# board.net
KiCad netlist of a schematic drawn in EAGLE
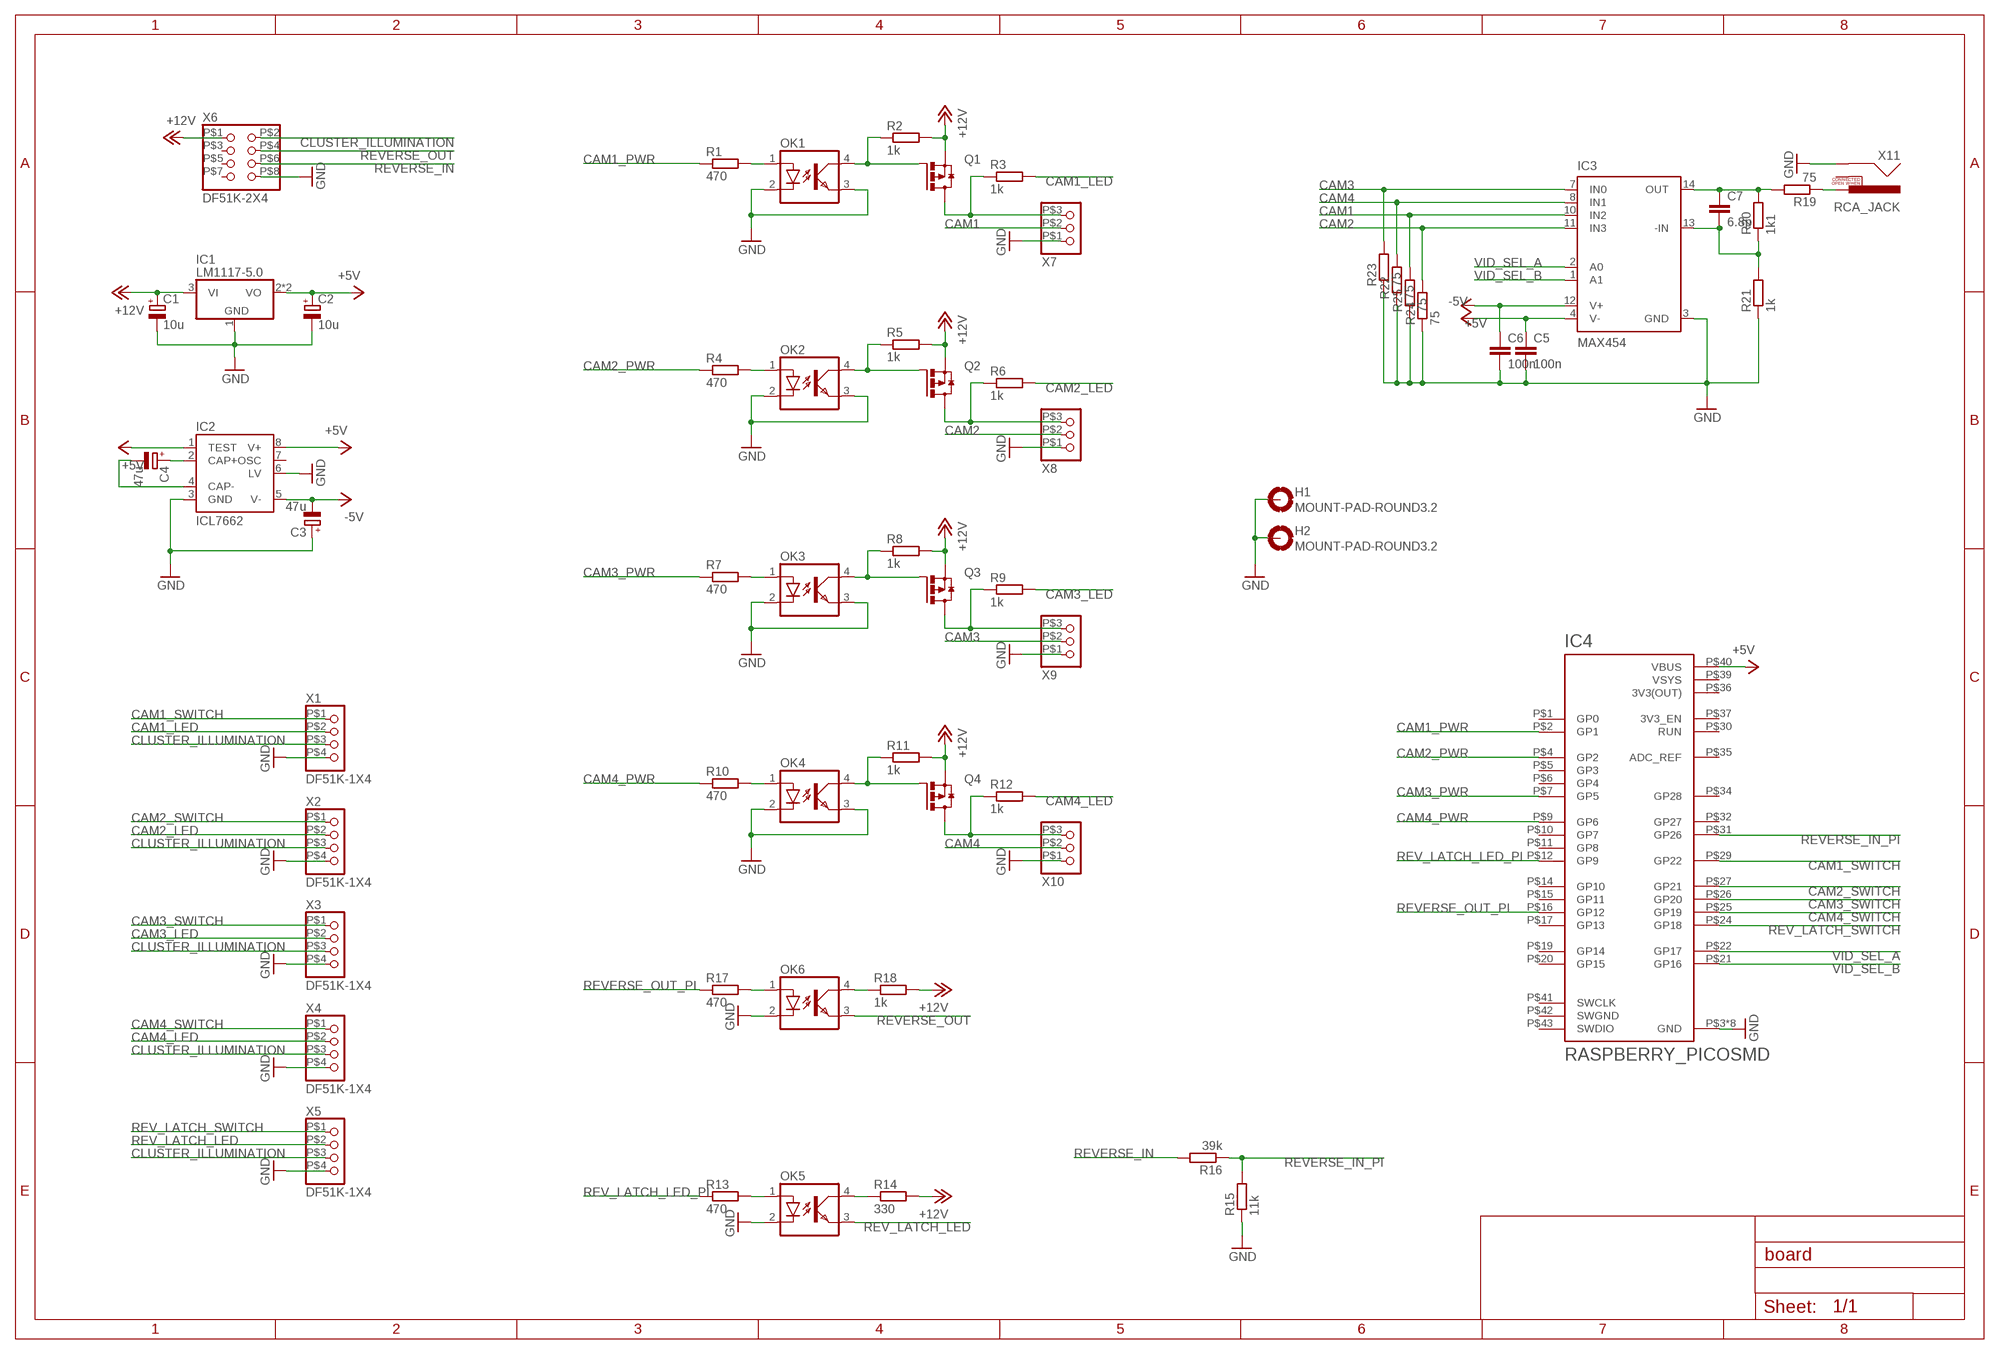
[diagram p0: schematic, sheet 1]

(export (version "E")
  (design (tool "Eeschema 10.0.6"))
  (components
    (comp (ref "C1")
      (value "10u")
      (footprint "eagle-import:C_4MM")
      (libsource (lib "eagle-import") (part "CAPACITOR_POL4MM^2"))
    )
    (comp (ref "C2")
      (value "10u")
      (footprint "eagle-import:C_4MM")
      (libsource (lib "eagle-import") (part "CAPACITOR_POL4MM^2"))
    )
    (comp (ref "C3")
      (value "47u")
      (footprint "eagle-import:CT7343")
      (libsource (lib "eagle-import") (part "CAPACITOR_POL2917"))
    )
    (comp (ref "C4")
      (value "47u")
      (footprint "eagle-import:CT7343")
      (libsource (lib "eagle-import") (part "CAPACITOR_POL2917"))
    )
    (comp (ref "C5")
      (value "100n")
      (footprint "eagle-import:C0805")
      (libsource (lib "eagle-import") (part "CAPACITOR0805"))
    )
    (comp (ref "C6")
      (value "100n")
      (footprint "eagle-import:C0805")
      (libsource (lib "eagle-import") (part "CAPACITOR0805"))
    )
    (comp (ref "C7")
      (value "6.8p")
      (footprint "eagle-import:C0805")
      (libsource (lib "eagle-import") (part "CAPACITOR0805"))
    )
    (comp (ref "H1")
      (value "MOUNT-PAD-ROUND3.2")
      (footprint "eagle-import:3,2-PAD")
      (libsource (lib "eagle-import") (part "MOUNT-PAD-ROUND3.2"))
    )
    (comp (ref "H2")
      (value "MOUNT-PAD-ROUND3.2")
      (footprint "eagle-import:3,2-PAD")
      (libsource (lib "eagle-import") (part "MOUNT-PAD-ROUND3.2"))
    )
    (comp (ref "IC1")
      (value "LM1117-5.0")
      (footprint "eagle-import:SOT223")
      (libsource (lib "eagle-import") (part "LM1117-3.3"))
    )
    (comp (ref "IC2")
      (value "ICL7662")
      (footprint "eagle-import:SO08")
      (libsource (lib "eagle-import") (part "ICL7662"))
    )
    (comp (ref "IC3")
      (value "MAX454")
      (footprint "eagle-import:DIL14")
      (libsource (lib "eagle-import") (part "MAX454"))
    )
    (comp (ref "IC4")
      (value "RASPBERRY_PICOSMD")
      (footprint "eagle-import:PICO-PKG-SMD")
      (libsource (lib "eagle-import") (part "RASPBERRY_PICOSMD"))
    )
    (comp (ref "OK1")
      (value "OPTOCOUPLERSO4")
      (footprint "eagle-import:SO04")
      (libsource (lib "eagle-import") (part "OPTOCOUPLERSO4"))
    )
    (comp (ref "OK2")
      (value "OPTOCOUPLERSO4")
      (footprint "eagle-import:SO04")
      (libsource (lib "eagle-import") (part "OPTOCOUPLERSO4"))
    )
    (comp (ref "OK3")
      (value "OPTOCOUPLERSO4")
      (footprint "eagle-import:SO04")
      (libsource (lib "eagle-import") (part "OPTOCOUPLERSO4"))
    )
    (comp (ref "OK4")
      (value "OPTOCOUPLERSO4")
      (footprint "eagle-import:SO04")
      (libsource (lib "eagle-import") (part "OPTOCOUPLERSO4"))
    )
    (comp (ref "OK5")
      (value "OPTOCOUPLERSO4")
      (footprint "eagle-import:SO04")
      (libsource (lib "eagle-import") (part "OPTOCOUPLERSO4"))
    )
    (comp (ref "OK6")
      (value "OPTOCOUPLERSO4")
      (footprint "eagle-import:SO04")
      (libsource (lib "eagle-import") (part "OPTOCOUPLERSO4"))
    )
    (comp (ref "Q1")
      (value "MOSFET_P_CHANNELSOT23")
      (footprint "eagle-import:SOT23")
      (libsource (lib "eagle-import") (part "MOSFET_P_CHANNELSOT23"))
    )
    (comp (ref "Q2")
      (value "MOSFET_P_CHANNELSOT23")
      (footprint "eagle-import:SOT23")
      (libsource (lib "eagle-import") (part "MOSFET_P_CHANNELSOT23"))
    )
    (comp (ref "Q3")
      (value "MOSFET_P_CHANNELSOT23")
      (footprint "eagle-import:SOT23")
      (libsource (lib "eagle-import") (part "MOSFET_P_CHANNELSOT23"))
    )
    (comp (ref "Q4")
      (value "MOSFET_P_CHANNELSOT23")
      (footprint "eagle-import:SOT23")
      (libsource (lib "eagle-import") (part "MOSFET_P_CHANNELSOT23"))
    )
    (comp (ref "R1")
      (value "470")
      (footprint "eagle-import:R0805")
      (libsource (lib "eagle-import") (part "RESISTOR0805"))
    )
    (comp (ref "R2")
      (value "1k")
      (footprint "eagle-import:R0805")
      (libsource (lib "eagle-import") (part "RESISTOR0805"))
    )
    (comp (ref "R3")
      (value "1k")
      (footprint "eagle-import:R0805")
      (libsource (lib "eagle-import") (part "RESISTOR0805"))
    )
    (comp (ref "R4")
      (value "470")
      (footprint "eagle-import:R0805")
      (libsource (lib "eagle-import") (part "RESISTOR0805"))
    )
    (comp (ref "R5")
      (value "1k")
      (footprint "eagle-import:R0805")
      (libsource (lib "eagle-import") (part "RESISTOR0805"))
    )
    (comp (ref "R6")
      (value "1k")
      (footprint "eagle-import:R0805")
      (libsource (lib "eagle-import") (part "RESISTOR0805"))
    )
    (comp (ref "R7")
      (value "470")
      (footprint "eagle-import:R0805")
      (libsource (lib "eagle-import") (part "RESISTOR0805"))
    )
    (comp (ref "R8")
      (value "1k")
      (footprint "eagle-import:R0805")
      (libsource (lib "eagle-import") (part "RESISTOR0805"))
    )
    (comp (ref "R9")
      (value "1k")
      (footprint "eagle-import:R0805")
      (libsource (lib "eagle-import") (part "RESISTOR0805"))
    )
    (comp (ref "R10")
      (value "470")
      (footprint "eagle-import:R0805")
      (libsource (lib "eagle-import") (part "RESISTOR0805"))
    )
    (comp (ref "R11")
      (value "1k")
      (footprint "eagle-import:R0805")
      (libsource (lib "eagle-import") (part "RESISTOR0805"))
    )
    (comp (ref "R12")
      (value "1k")
      (footprint "eagle-import:R0805")
      (libsource (lib "eagle-import") (part "RESISTOR0805"))
    )
    (comp (ref "R13")
      (value "470")
      (footprint "eagle-import:R0805")
      (libsource (lib "eagle-import") (part "RESISTOR0805"))
    )
    (comp (ref "R14")
      (value "330")
      (footprint "eagle-import:R0805")
      (libsource (lib "eagle-import") (part "RESISTOR0805"))
    )
    (comp (ref "R15")
      (value "11k")
      (footprint "eagle-import:R0805")
      (libsource (lib "eagle-import") (part "RESISTOR0805"))
    )
    (comp (ref "R16")
      (value "39k")
      (footprint "eagle-import:R0805")
      (libsource (lib "eagle-import") (part "RESISTOR0805"))
    )
    (comp (ref "R17")
      (value "470")
      (footprint "eagle-import:R0805")
      (libsource (lib "eagle-import") (part "RESISTOR0805"))
    )
    (comp (ref "R18")
      (value "1k")
      (footprint "eagle-import:R0805")
      (libsource (lib "eagle-import") (part "RESISTOR0805"))
    )
    (comp (ref "R19")
      (value "75")
      (footprint "eagle-import:R0805")
      (libsource (lib "eagle-import") (part "RESISTOR0805"))
    )
    (comp (ref "R20")
      (value "1k1")
      (footprint "eagle-import:R0805")
      (libsource (lib "eagle-import") (part "RESISTOR0805"))
    )
    (comp (ref "R21")
      (value "1k")
      (footprint "eagle-import:R0805")
      (libsource (lib "eagle-import") (part "RESISTOR0805"))
    )
    (comp (ref "R22")
      (value "75")
      (footprint "eagle-import:R0805")
      (libsource (lib "eagle-import") (part "RESISTOR0805"))
    )
    (comp (ref "R23")
      (value "75")
      (footprint "eagle-import:R0805")
      (libsource (lib "eagle-import") (part "RESISTOR0805"))
    )
    (comp (ref "R24")
      (value "75")
      (footprint "eagle-import:R0805")
      (libsource (lib "eagle-import") (part "RESISTOR0805"))
    )
    (comp (ref "R25")
      (value "75")
      (footprint "eagle-import:R0805")
      (libsource (lib "eagle-import") (part "RESISTOR0805"))
    )
    (comp (ref "X1")
      (value "DF51K-1X4")
      (footprint "eagle-import:DF51K-1X4")
      (libsource (lib "eagle-import") (part "DF51K-1X4"))
    )
    (comp (ref "X2")
      (value "DF51K-1X4")
      (footprint "eagle-import:DF51K-1X4")
      (libsource (lib "eagle-import") (part "DF51K-1X4"))
    )
    (comp (ref "X3")
      (value "DF51K-1X4")
      (footprint "eagle-import:DF51K-1X4")
      (libsource (lib "eagle-import") (part "DF51K-1X4"))
    )
    (comp (ref "X4")
      (value "DF51K-1X4")
      (footprint "eagle-import:DF51K-1X4")
      (libsource (lib "eagle-import") (part "DF51K-1X4"))
    )
    (comp (ref "X5")
      (value "DF51K-1X4")
      (footprint "eagle-import:DF51K-1X4")
      (libsource (lib "eagle-import") (part "DF51K-1X4"))
    )
    (comp (ref "X6")
      (value "DF51K-2X4")
      (footprint "eagle-import:DF51K-2X4")
      (libsource (lib "eagle-import") (part "DF51K-2X4"))
    )
    (comp (ref "X7")
      (value "JST_XH_1X3")
      (footprint "eagle-import:JST_XH_1X3")
      (libsource (lib "eagle-import") (part "JST_XH_1X3"))
    )
    (comp (ref "X8")
      (value "JST_XH_1X3")
      (footprint "eagle-import:JST_XH_1X3")
      (libsource (lib "eagle-import") (part "JST_XH_1X3"))
    )
    (comp (ref "X9")
      (value "JST_XH_1X3")
      (footprint "eagle-import:JST_XH_1X3")
      (libsource (lib "eagle-import") (part "JST_XH_1X3"))
    )
    (comp (ref "X10")
      (value "JST_XH_1X3")
      (footprint "eagle-import:JST_XH_1X3")
      (libsource (lib "eagle-import") (part "JST_XH_1X3"))
    )
    (comp (ref "X11")
      (value "RCA_JACK")
      (footprint "eagle-import:RCA_JACK")
      (libsource (lib "eagle-import") (part "RCA_JACK"))
    )
  )
  (nets
    (net (code "1") (name "+5V") (class "Default")
      (node (ref "C2") (pin "+") (pinfunction "+_+") (pintype "passive"))
      (node (ref "C6") (pin "1") (pinfunction "1_1") (pintype "passive"))
      (node (ref "IC1") (pin "2") (pinfunction "VO_2") (pintype "passive"))
      (node (ref "IC1") (pin "4") (pinfunction "VO_4") (pintype "passive"))
      (node (ref "IC2") (pin "1") (pinfunction "TEST_1") (pintype "bidirectional"))
      (node (ref "IC2") (pin "8") (pinfunction "V+_8") (pintype "bidirectional"))
      (node (ref "IC3") (pin "12") (pinfunction "V+_12") (pintype "bidirectional"))
      (node (ref "IC4") (pin "P$40") (pinfunction "VBUS_P$40") (pintype "power_in"))
    )
    (net (code "2") (name "+12V") (class "Default")
      (node (ref "C1") (pin "+") (pinfunction "+_+") (pintype "passive"))
      (node (ref "IC1") (pin "3") (pinfunction "VI_3") (pintype "input"))
      (node (ref "Q1") (pin "2") (pinfunction "S_2") (pintype "passive"))
      (node (ref "Q2") (pin "2") (pinfunction "S_2") (pintype "passive"))
      (node (ref "Q3") (pin "2") (pinfunction "S_2") (pintype "passive"))
      (node (ref "Q4") (pin "2") (pinfunction "S_2") (pintype "passive"))
      (node (ref "R11") (pin "2") (pinfunction "2_2") (pintype "passive"))
      (node (ref "R14") (pin "2") (pinfunction "2_2") (pintype "passive"))
      (node (ref "R18") (pin "2") (pinfunction "2_2") (pintype "passive"))
      (node (ref "R2") (pin "2") (pinfunction "2_2") (pintype "passive"))
      (node (ref "R5") (pin "2") (pinfunction "2_2") (pintype "passive"))
      (node (ref "R8") (pin "2") (pinfunction "2_2") (pintype "passive"))
      (node (ref "X6") (pin "P$1") (pinfunction "1_P$1") (pintype "passive"))
    )
    (net (code "3") (name "-5V") (class "Default")
      (node (ref "C3") (pin "-") (pinfunction "-_-") (pintype "passive"))
      (node (ref "C5") (pin "1") (pinfunction "1_1") (pintype "passive"))
      (node (ref "IC2") (pin "5") (pinfunction "V-_5") (pintype "bidirectional"))
      (node (ref "IC3") (pin "4") (pinfunction "V-_4") (pintype "bidirectional"))
    )
    (net (code "4") (name "/3V3(OUT)") (class "Default")
      (node (ref "IC4") (pin "P$36") (pinfunction "3V3(OUT)_P$36") (pintype "power_in"))
    )
    (net (code "5") (name "/CAM1") (class "Default")
      (node (ref "IC3") (pin "10") (pinfunction "IN2_10") (pintype "bidirectional"))
      (node (ref "R25") (pin "2") (pinfunction "2_2") (pintype "passive"))
      (node (ref "X7") (pin "P$2") (pinfunction "2_P$2") (pintype "passive"))
    )
    (net (code "6") (name "/CAM1_LED") (class "Default")
      (node (ref "R3") (pin "2") (pinfunction "2_2") (pintype "passive"))
      (node (ref "X1") (pin "P$2") (pinfunction "2_P$2") (pintype "passive"))
    )
    (net (code "7") (name "/CAM1_PWR") (class "Default")
      (node (ref "IC4") (pin "P$2") (pinfunction "GP1_P$2") (pintype "bidirectional"))
      (node (ref "R1") (pin "1") (pinfunction "1_1") (pintype "passive"))
    )
    (net (code "8") (name "/CAM1_SWITCH") (class "Default")
      (node (ref "IC4") (pin "P$29") (pinfunction "GP22_P$29") (pintype "bidirectional"))
      (node (ref "X1") (pin "P$1") (pinfunction "1_P$1") (pintype "passive"))
    )
    (net (code "9") (name "/CAM2") (class "Default")
      (node (ref "IC3") (pin "11") (pinfunction "IN3_11") (pintype "bidirectional"))
      (node (ref "R24") (pin "2") (pinfunction "2_2") (pintype "passive"))
      (node (ref "X8") (pin "P$2") (pinfunction "2_P$2") (pintype "passive"))
    )
    (net (code "10") (name "/CAM2_LED") (class "Default")
      (node (ref "R6") (pin "2") (pinfunction "2_2") (pintype "passive"))
      (node (ref "X2") (pin "P$2") (pinfunction "2_P$2") (pintype "passive"))
    )
    (net (code "11") (name "/CAM2_PWR") (class "Default")
      (node (ref "IC4") (pin "P$4") (pinfunction "GP2_P$4") (pintype "bidirectional"))
      (node (ref "R4") (pin "1") (pinfunction "1_1") (pintype "passive"))
    )
    (net (code "12") (name "/CAM2_SWITCH") (class "Default")
      (node (ref "IC4") (pin "P$27") (pinfunction "GP21_P$27") (pintype "bidirectional"))
      (node (ref "X2") (pin "P$1") (pinfunction "1_P$1") (pintype "passive"))
    )
    (net (code "13") (name "/CAM3") (class "Default")
      (node (ref "IC3") (pin "7") (pinfunction "IN0_7") (pintype "bidirectional"))
      (node (ref "R23") (pin "2") (pinfunction "2_2") (pintype "passive"))
      (node (ref "X9") (pin "P$2") (pinfunction "2_P$2") (pintype "passive"))
    )
    (net (code "14") (name "/CAM3_LED") (class "Default")
      (node (ref "R9") (pin "2") (pinfunction "2_2") (pintype "passive"))
      (node (ref "X3") (pin "P$2") (pinfunction "2_P$2") (pintype "passive"))
    )
    (net (code "15") (name "/CAM3_PWR") (class "Default")
      (node (ref "IC4") (pin "P$7") (pinfunction "GP5_P$7") (pintype "bidirectional"))
      (node (ref "R7") (pin "1") (pinfunction "1_1") (pintype "passive"))
    )
    (net (code "16") (name "/CAM3_SWITCH") (class "Default")
      (node (ref "IC4") (pin "P$26") (pinfunction "GP20_P$26") (pintype "bidirectional"))
      (node (ref "X3") (pin "P$1") (pinfunction "1_P$1") (pintype "passive"))
    )
    (net (code "17") (name "/CAM4") (class "Default")
      (node (ref "IC3") (pin "8") (pinfunction "IN1_8") (pintype "bidirectional"))
      (node (ref "R22") (pin "2") (pinfunction "2_2") (pintype "passive"))
      (node (ref "X10") (pin "P$2") (pinfunction "2_P$2") (pintype "passive"))
    )
    (net (code "18") (name "/CAM4_LED") (class "Default")
      (node (ref "R12") (pin "2") (pinfunction "2_2") (pintype "passive"))
      (node (ref "X4") (pin "P$2") (pinfunction "2_P$2") (pintype "passive"))
    )
    (net (code "19") (name "/CAM4_PWR") (class "Default")
      (node (ref "IC4") (pin "P$9") (pinfunction "GP6_P$9") (pintype "bidirectional"))
      (node (ref "R10") (pin "1") (pinfunction "1_1") (pintype "passive"))
    )
    (net (code "20") (name "/CAM4_SWITCH") (class "Default")
      (node (ref "IC4") (pin "P$25") (pinfunction "GP19_P$25") (pintype "bidirectional"))
      (node (ref "X4") (pin "P$1") (pinfunction "1_P$1") (pintype "passive"))
    )
    (net (code "21") (name "/CLUSTER_ILLUMINATION") (class "Default")
      (node (ref "X1") (pin "P$3") (pinfunction "3_P$3") (pintype "passive"))
      (node (ref "X2") (pin "P$3") (pinfunction "3_P$3") (pintype "passive"))
      (node (ref "X3") (pin "P$3") (pinfunction "3_P$3") (pintype "passive"))
      (node (ref "X4") (pin "P$3") (pinfunction "3_P$3") (pintype "passive"))
      (node (ref "X5") (pin "P$3") (pinfunction "3_P$3") (pintype "passive"))
      (node (ref "X6") (pin "P$2") (pinfunction "2_P$2") (pintype "passive"))
    )
    (net (code "22") (name "/REVERSE_IN") (class "Default")
      (node (ref "R16") (pin "2") (pinfunction "2_2") (pintype "passive"))
      (node (ref "X6") (pin "P$6") (pinfunction "6_P$6") (pintype "passive"))
    )
    (net (code "23") (name "/REVERSE_IN_PI") (class "Default")
      (node (ref "IC4") (pin "P$31") (pinfunction "GP26_P$31") (pintype "bidirectional"))
      (node (ref "R15") (pin "2") (pinfunction "2_2") (pintype "passive"))
      (node (ref "R16") (pin "1") (pinfunction "1_1") (pintype "passive"))
    )
    (net (code "24") (name "/REVERSE_OUT") (class "Default")
      (node (ref "OK6") (pin "3") (pinfunction "EMIT_3") (pintype "passive"))
      (node (ref "X6") (pin "P$4") (pinfunction "4_P$4") (pintype "passive"))
    )
    (net (code "25") (name "/REVERSE_OUT_PI") (class "Default")
      (node (ref "IC4") (pin "P$16") (pinfunction "GP12_P$16") (pintype "bidirectional"))
      (node (ref "R17") (pin "1") (pinfunction "1_1") (pintype "passive"))
    )
    (net (code "26") (name "/REV_LATCH_LED") (class "Default")
      (node (ref "OK5") (pin "3") (pinfunction "EMIT_3") (pintype "passive"))
      (node (ref "X5") (pin "P$2") (pinfunction "2_P$2") (pintype "passive"))
    )
    (net (code "27") (name "/REV_LATCH_LED_PI") (class "Default")
      (node (ref "IC4") (pin "P$12") (pinfunction "GP9_P$12") (pintype "bidirectional"))
      (node (ref "R13") (pin "1") (pinfunction "1_1") (pintype "passive"))
    )
    (net (code "28") (name "/REV_LATCH_SWITCH") (class "Default")
      (node (ref "IC4") (pin "P$24") (pinfunction "GP18_P$24") (pintype "bidirectional"))
      (node (ref "X5") (pin "P$1") (pinfunction "1_P$1") (pintype "passive"))
    )
    (net (code "29") (name "/SWGND") (class "Default")
      (node (ref "IC4") (pin "P$42") (pinfunction "SWGND_P$42") (pintype "power_in"))
    )
    (net (code "30") (name "/VID_SEL_A") (class "Default")
      (node (ref "IC3") (pin "2") (pinfunction "A0_2") (pintype "bidirectional"))
      (node (ref "IC4") (pin "P$22") (pinfunction "GP17_P$22") (pintype "bidirectional"))
    )
    (net (code "31") (name "/VID_SEL_B") (class "Default")
      (node (ref "IC3") (pin "1") (pinfunction "A1_1") (pintype "bidirectional"))
      (node (ref "IC4") (pin "P$21") (pinfunction "GP16_P$21") (pintype "bidirectional"))
    )
    (net (code "32") (name "/VSYS") (class "Default")
      (node (ref "IC4") (pin "P$39") (pinfunction "VSYS_P$39") (pintype "power_in"))
    )
    (net (code "33") (name "GND") (class "Default")
      (node (ref "C1") (pin "-") (pinfunction "-_-") (pintype "passive"))
      (node (ref "C2") (pin "-") (pinfunction "-_-") (pintype "passive"))
      (node (ref "C3") (pin "+") (pinfunction "+_+") (pintype "passive"))
      (node (ref "C5") (pin "2") (pinfunction "2_2") (pintype "passive"))
      (node (ref "C6") (pin "2") (pinfunction "2_2") (pintype "passive"))
      (node (ref "H1") (pin "B3,2") (pinfunction "MOUNT_B3,2") (pintype "passive"))
      (node (ref "H1") (pin "P$1") (pinfunction "MOUNT_P$1") (pintype "passive"))
      (node (ref "H1") (pin "P$2") (pinfunction "MOUNT_P$2") (pintype "passive"))
      (node (ref "H1") (pin "P$3") (pinfunction "MOUNT_P$3") (pintype "passive"))
      (node (ref "H1") (pin "P$4") (pinfunction "MOUNT_P$4") (pintype "passive"))
      (node (ref "H1") (pin "P$5") (pinfunction "MOUNT_P$5") (pintype "passive"))
      (node (ref "H1") (pin "P$6") (pinfunction "MOUNT_P$6") (pintype "passive"))
      (node (ref "H1") (pin "P$7") (pinfunction "MOUNT_P$7") (pintype "passive"))
      (node (ref "H1") (pin "P$8") (pinfunction "MOUNT_P$8") (pintype "passive"))
      (node (ref "H2") (pin "B3,2") (pinfunction "MOUNT_B3,2") (pintype "passive"))
      (node (ref "H2") (pin "P$1") (pinfunction "MOUNT_P$1") (pintype "passive"))
      (node (ref "H2") (pin "P$2") (pinfunction "MOUNT_P$2") (pintype "passive"))
      (node (ref "H2") (pin "P$3") (pinfunction "MOUNT_P$3") (pintype "passive"))
      (node (ref "H2") (pin "P$4") (pinfunction "MOUNT_P$4") (pintype "passive"))
      (node (ref "H2") (pin "P$5") (pinfunction "MOUNT_P$5") (pintype "passive"))
      (node (ref "H2") (pin "P$6") (pinfunction "MOUNT_P$6") (pintype "passive"))
      (node (ref "H2") (pin "P$7") (pinfunction "MOUNT_P$7") (pintype "passive"))
      (node (ref "H2") (pin "P$8") (pinfunction "MOUNT_P$8") (pintype "passive"))
      (node (ref "IC1") (pin "1") (pinfunction "GND_1") (pintype "passive"))
      (node (ref "IC2") (pin "3") (pinfunction "GND_3") (pintype "bidirectional"))
      (node (ref "IC2") (pin "6") (pinfunction "LV_6") (pintype "bidirectional"))
      (node (ref "IC3") (pin "3") (pinfunction "GND_3") (pintype "bidirectional"))
      (node (ref "IC4") (pin "P$13") (pinfunction "GND_P$13") (pintype "power_in"))
      (node (ref "IC4") (pin "P$18") (pinfunction "GND_P$18") (pintype "power_in"))
      (node (ref "IC4") (pin "P$23") (pinfunction "GND_P$23") (pintype "power_in"))
      (node (ref "IC4") (pin "P$28") (pinfunction "GND_P$28") (pintype "power_in"))
      (node (ref "IC4") (pin "P$3") (pinfunction "GND_P$3") (pintype "power_in"))
      (node (ref "IC4") (pin "P$33") (pinfunction "GND_P$33") (pintype "power_in"))
      (node (ref "IC4") (pin "P$38") (pinfunction "GND_P$38") (pintype "power_in"))
      (node (ref "IC4") (pin "P$8") (pinfunction "GND_P$8") (pintype "power_in"))
      (node (ref "OK1") (pin "2") (pinfunction "C_2") (pintype "passive"))
      (node (ref "OK1") (pin "3") (pinfunction "EMIT_3") (pintype "passive"))
      (node (ref "OK2") (pin "2") (pinfunction "C_2") (pintype "passive"))
      (node (ref "OK2") (pin "3") (pinfunction "EMIT_3") (pintype "passive"))
      (node (ref "OK3") (pin "2") (pinfunction "C_2") (pintype "passive"))
      (node (ref "OK3") (pin "3") (pinfunction "EMIT_3") (pintype "passive"))
      (node (ref "OK4") (pin "2") (pinfunction "C_2") (pintype "passive"))
      (node (ref "OK4") (pin "3") (pinfunction "EMIT_3") (pintype "passive"))
      (node (ref "OK5") (pin "2") (pinfunction "C_2") (pintype "passive"))
      (node (ref "OK6") (pin "2") (pinfunction "C_2") (pintype "passive"))
      (node (ref "R15") (pin "1") (pinfunction "1_1") (pintype "passive"))
      (node (ref "R21") (pin "1") (pinfunction "1_1") (pintype "passive"))
      (node (ref "R22") (pin "1") (pinfunction "1_1") (pintype "passive"))
      (node (ref "R23") (pin "1") (pinfunction "1_1") (pintype "passive"))
      (node (ref "R24") (pin "1") (pinfunction "1_1") (pintype "passive"))
      (node (ref "R25") (pin "1") (pinfunction "1_1") (pintype "passive"))
      (node (ref "X1") (pin "P$4") (pinfunction "4_P$4") (pintype "passive"))
      (node (ref "X10") (pin "P$1") (pinfunction "1_P$1") (pintype "passive"))
      (node (ref "X11") (pin "1") (pinfunction "SHELL_1") (pintype "bidirectional"))
      (node (ref "X2") (pin "P$4") (pinfunction "4_P$4") (pintype "passive"))
      (node (ref "X3") (pin "P$4") (pinfunction "4_P$4") (pintype "passive"))
      (node (ref "X4") (pin "P$4") (pinfunction "4_P$4") (pintype "passive"))
      (node (ref "X5") (pin "P$4") (pinfunction "4_P$4") (pintype "passive"))
      (node (ref "X6") (pin "P$8") (pinfunction "8_P$8") (pintype "passive"))
      (node (ref "X7") (pin "P$1") (pinfunction "1_P$1") (pintype "passive"))
      (node (ref "X8") (pin "P$1") (pinfunction "1_P$1") (pintype "passive"))
      (node (ref "X9") (pin "P$1") (pinfunction "1_P$1") (pintype "passive"))
    )
    (net (code "34") (name "Net-(IC2-CAP+)") (class "Default")
      (node (ref "C4") (pin "+") (pinfunction "+_+") (pintype "passive"))
      (node (ref "IC2") (pin "2") (pinfunction "CAP+_2") (pintype "bidirectional"))
    )
    (net (code "35") (name "Net-(IC2-CAP-)") (class "Default")
      (node (ref "C4") (pin "-") (pinfunction "-_-") (pintype "passive"))
      (node (ref "IC2") (pin "4") (pinfunction "CAP-_4") (pintype "bidirectional"))
    )
    (net (code "36") (name "Net-(IC3--IN)") (class "Default")
      (node (ref "C7") (pin "2") (pinfunction "2_2") (pintype "passive"))
      (node (ref "IC3") (pin "13") (pinfunction "-IN_13") (pintype "bidirectional"))
      (node (ref "R20") (pin "1") (pinfunction "1_1") (pintype "passive"))
      (node (ref "R21") (pin "2") (pinfunction "2_2") (pintype "passive"))
    )
    (net (code "37") (name "Net-(IC3-OUT)") (class "Default")
      (node (ref "C7") (pin "1") (pinfunction "1_1") (pintype "passive"))
      (node (ref "IC3") (pin "14") (pinfunction "OUT_14") (pintype "bidirectional"))
      (node (ref "R19") (pin "2") (pinfunction "2_2") (pintype "passive"))
      (node (ref "R20") (pin "2") (pinfunction "2_2") (pintype "passive"))
    )
    (net (code "38") (name "Net-(OK1-A)") (class "Default")
      (node (ref "OK1") (pin "1") (pinfunction "A_1") (pintype "passive"))
      (node (ref "R1") (pin "2") (pinfunction "2_2") (pintype "passive"))
    )
    (net (code "39") (name "Net-(OK1-COL)") (class "Default")
      (node (ref "OK1") (pin "4") (pinfunction "COL_4") (pintype "passive"))
      (node (ref "Q1") (pin "1") (pinfunction "G_1") (pintype "passive"))
      (node (ref "R2") (pin "1") (pinfunction "1_1") (pintype "passive"))
    )
    (net (code "40") (name "Net-(OK2-A)") (class "Default")
      (node (ref "OK2") (pin "1") (pinfunction "A_1") (pintype "passive"))
      (node (ref "R4") (pin "2") (pinfunction "2_2") (pintype "passive"))
    )
    (net (code "41") (name "Net-(OK2-COL)") (class "Default")
      (node (ref "OK2") (pin "4") (pinfunction "COL_4") (pintype "passive"))
      (node (ref "Q2") (pin "1") (pinfunction "G_1") (pintype "passive"))
      (node (ref "R5") (pin "1") (pinfunction "1_1") (pintype "passive"))
    )
    (net (code "42") (name "Net-(OK3-A)") (class "Default")
      (node (ref "OK3") (pin "1") (pinfunction "A_1") (pintype "passive"))
      (node (ref "R7") (pin "2") (pinfunction "2_2") (pintype "passive"))
    )
    (net (code "43") (name "Net-(OK3-COL)") (class "Default")
      (node (ref "OK3") (pin "4") (pinfunction "COL_4") (pintype "passive"))
      (node (ref "Q3") (pin "1") (pinfunction "G_1") (pintype "passive"))
      (node (ref "R8") (pin "1") (pinfunction "1_1") (pintype "passive"))
    )
    (net (code "44") (name "Net-(OK4-A)") (class "Default")
      (node (ref "OK4") (pin "1") (pinfunction "A_1") (pintype "passive"))
      (node (ref "R10") (pin "2") (pinfunction "2_2") (pintype "passive"))
    )
    (net (code "45") (name "Net-(OK4-COL)") (class "Default")
      (node (ref "OK4") (pin "4") (pinfunction "COL_4") (pintype "passive"))
      (node (ref "Q4") (pin "1") (pinfunction "G_1") (pintype "passive"))
      (node (ref "R11") (pin "1") (pinfunction "1_1") (pintype "passive"))
    )
    (net (code "46") (name "Net-(OK5-A)") (class "Default")
      (node (ref "OK5") (pin "1") (pinfunction "A_1") (pintype "passive"))
      (node (ref "R13") (pin "2") (pinfunction "2_2") (pintype "passive"))
    )
    (net (code "47") (name "Net-(OK5-COL)") (class "Default")
      (node (ref "OK5") (pin "4") (pinfunction "COL_4") (pintype "passive"))
      (node (ref "R14") (pin "1") (pinfunction "1_1") (pintype "passive"))
    )
    (net (code "48") (name "Net-(OK6-A)") (class "Default")
      (node (ref "OK6") (pin "1") (pinfunction "A_1") (pintype "passive"))
      (node (ref "R17") (pin "2") (pinfunction "2_2") (pintype "passive"))
    )
    (net (code "49") (name "Net-(OK6-COL)") (class "Default")
      (node (ref "OK6") (pin "4") (pinfunction "COL_4") (pintype "passive"))
      (node (ref "R18") (pin "1") (pinfunction "1_1") (pintype "passive"))
    )
    (net (code "50") (name "Net-(Q1-D)") (class "Default")
      (node (ref "Q1") (pin "3") (pinfunction "D_3") (pintype "passive"))
      (node (ref "R3") (pin "1") (pinfunction "1_1") (pintype "passive"))
      (node (ref "X7") (pin "P$3") (pinfunction "3_P$3") (pintype "passive"))
    )
    (net (code "51") (name "Net-(Q2-D)") (class "Default")
      (node (ref "Q2") (pin "3") (pinfunction "D_3") (pintype "passive"))
      (node (ref "R6") (pin "1") (pinfunction "1_1") (pintype "passive"))
      (node (ref "X8") (pin "P$3") (pinfunction "3_P$3") (pintype "passive"))
    )
    (net (code "52") (name "Net-(Q3-D)") (class "Default")
      (node (ref "Q3") (pin "3") (pinfunction "D_3") (pintype "passive"))
      (node (ref "R9") (pin "1") (pinfunction "1_1") (pintype "passive"))
      (node (ref "X9") (pin "P$3") (pinfunction "3_P$3") (pintype "passive"))
    )
    (net (code "53") (name "Net-(Q4-D)") (class "Default")
      (node (ref "Q4") (pin "3") (pinfunction "D_3") (pintype "passive"))
      (node (ref "R12") (pin "1") (pinfunction "1_1") (pintype "passive"))
      (node (ref "X10") (pin "P$3") (pinfunction "3_P$3") (pintype "passive"))
    )
    (net (code "54") (name "Net-(X11-PIN)") (class "Default")
      (node (ref "R19") (pin "1") (pinfunction "1_1") (pintype "passive"))
      (node (ref "X11") (pin "3") (pinfunction "PIN_3") (pintype "bidirectional"))
    )
    (net (code "55") (name "unconnected-(IC2-OSC-Pad7)") (class "Default")
      (node (ref "IC2") (pin "7") (pinfunction "OSC_7") (pintype "bidirectional"))
    )
    (net (code "56") (name "unconnected-(IC4-3V3_EN-PadP$37)") (class "Default")
      (node (ref "IC4") (pin "P$37") (pinfunction "3V3_EN_P$37") (pintype "input"))
    )
    (net (code "57") (name "unconnected-(IC4-ADC_REF-PadP$35)") (class "Default")
      (node (ref "IC4") (pin "P$35") (pinfunction "ADC_REF_P$35") (pintype "input"))
    )
    (net (code "58") (name "unconnected-(IC4-GP0-PadP$1)") (class "Default")
      (node (ref "IC4") (pin "P$1") (pinfunction "GP0_P$1") (pintype "bidirectional"))
    )
    (net (code "59") (name "unconnected-(IC4-GP3-PadP$5)") (class "Default")
      (node (ref "IC4") (pin "P$5") (pinfunction "GP3_P$5") (pintype "bidirectional"))
    )
    (net (code "60") (name "unconnected-(IC4-GP4-PadP$6)") (class "Default")
      (node (ref "IC4") (pin "P$6") (pinfunction "GP4_P$6") (pintype "bidirectional"))
    )
    (net (code "61") (name "unconnected-(IC4-GP7-PadP$10)") (class "Default")
      (node (ref "IC4") (pin "P$10") (pinfunction "GP7_P$10") (pintype "bidirectional"))
    )
    (net (code "62") (name "unconnected-(IC4-GP8-PadP$11)") (class "Default")
      (node (ref "IC4") (pin "P$11") (pinfunction "GP8_P$11") (pintype "bidirectional"))
    )
    (net (code "63") (name "unconnected-(IC4-GP10-PadP$14)") (class "Default")
      (node (ref "IC4") (pin "P$14") (pinfunction "GP10_P$14") (pintype "bidirectional"))
    )
    (net (code "64") (name "unconnected-(IC4-GP11-PadP$15)") (class "Default")
      (node (ref "IC4") (pin "P$15") (pinfunction "GP11_P$15") (pintype "bidirectional"))
    )
    (net (code "65") (name "unconnected-(IC4-GP13-PadP$17)") (class "Default")
      (node (ref "IC4") (pin "P$17") (pinfunction "GP13_P$17") (pintype "bidirectional"))
    )
    (net (code "66") (name "unconnected-(IC4-GP14-PadP$19)") (class "Default")
      (node (ref "IC4") (pin "P$19") (pinfunction "GP14_P$19") (pintype "bidirectional"))
    )
    (net (code "67") (name "unconnected-(IC4-GP15-PadP$20)") (class "Default")
      (node (ref "IC4") (pin "P$20") (pinfunction "GP15_P$20") (pintype "bidirectional"))
    )
    (net (code "68") (name "unconnected-(IC4-GP27-PadP$32)") (class "Default")
      (node (ref "IC4") (pin "P$32") (pinfunction "GP27_P$32") (pintype "bidirectional"))
    )
    (net (code "69") (name "unconnected-(IC4-GP28-PadP$34)") (class "Default")
      (node (ref "IC4") (pin "P$34") (pinfunction "GP28_P$34") (pintype "bidirectional"))
    )
    (net (code "70") (name "unconnected-(IC4-RUN-PadP$30)") (class "Default")
      (node (ref "IC4") (pin "P$30") (pinfunction "RUN_P$30") (pintype "input"))
    )
    (net (code "71") (name "unconnected-(IC4-SWCLK-PadP$41)") (class "Default")
      (node (ref "IC4") (pin "P$41") (pinfunction "SWCLK_P$41") (pintype "input"))
    )
    (net (code "72") (name "unconnected-(IC4-SWDIO-PadP$43)") (class "Default")
      (node (ref "IC4") (pin "P$43") (pinfunction "SWDIO_P$43") (pintype "bidirectional"))
    )
    (net (code "73") (name "unconnected-(X6-3-PadP$3)") (class "Default")
      (node (ref "X6") (pin "P$3") (pinfunction "3_P$3") (pintype "passive"))
    )
    (net (code "74") (name "unconnected-(X6-5-PadP$5)") (class "Default")
      (node (ref "X6") (pin "P$5") (pinfunction "5_P$5") (pintype "passive"))
    )
    (net (code "75") (name "unconnected-(X6-7-PadP$7)") (class "Default")
      (node (ref "X6") (pin "P$7") (pinfunction "7_P$7") (pintype "passive"))
    )
    (net (code "76") (name "unconnected-(X11-SWITCH-Pad4)") (class "Default")
      (node (ref "X11") (pin "4") (pinfunction "SWITCH_4") (pintype "bidirectional"))
    )
  )
)
